# design.net
KiCad netlist of a schematic drawn in Altium Designer
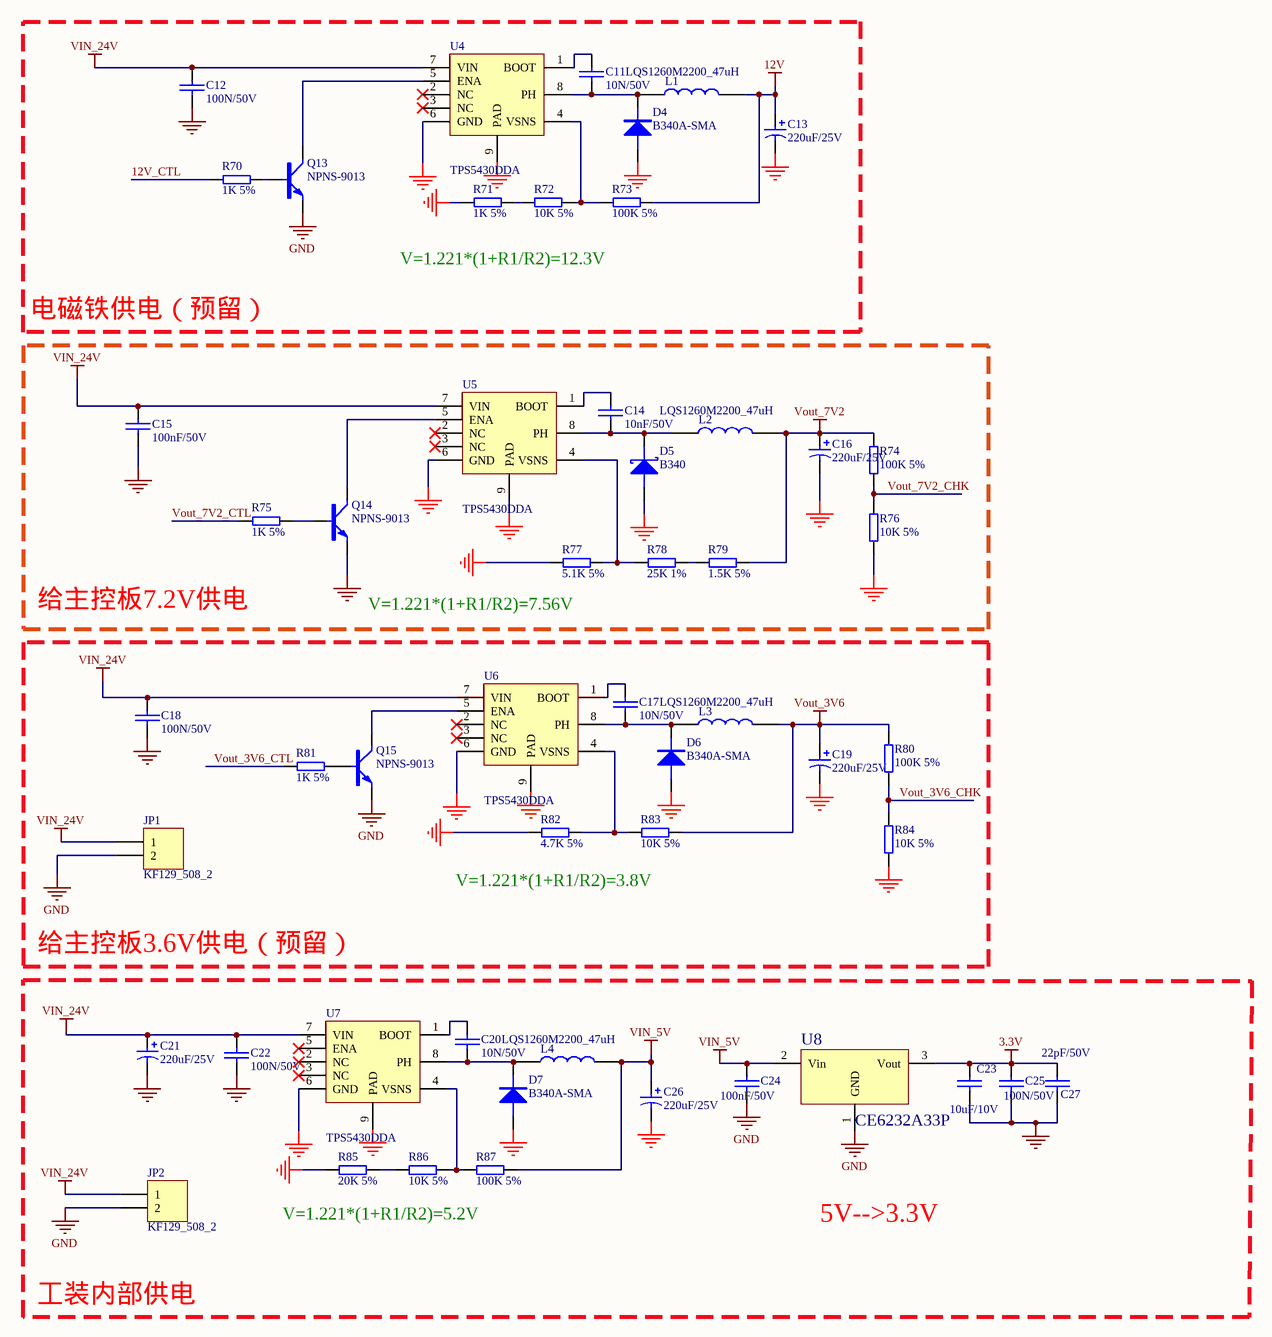
[diagram p0: 电源.SchDoc]

(export (version "E")
  (design (tool "Eeschema 10.0.6"))
  (components
    (comp (ref "C11")
      (value "10N/50V")
      (footprint "CAP0603")
      (description "10N/50V，±10%，0603")
      (fields (field (name "PART NUMBER") "101020103-0007"))
      (libsource (lib "Database_Libs1") (part "CC03K7R9B_10N"))
    )
    (comp (ref "C12")
      (value "100N/50V")
      (footprint "CAP0603")
      (description "100N/50V，±10%，0603")
      (fields (field (name "PART NUMBER") "101020103-0021"))
      (libsource (lib "Database_Libs1") (part "CC03K7R9B_100N"))
    )
    (comp (ref "C13")
      (value "220uF/25V")
      (footprint "220uF 25V")
      (description "220UF,25 V,±20%,8*10mm,立隆电子工业股份有限公司,VEJ221M1ETR-0810")
      (libsource (lib "转接板封装") (part "220uF/25V"))
    )
    (comp (ref "C14")
      (value "10nF/50V")
      (footprint "CAP0603")
      (description "10nF,50 V,±10%,0603,X7R,国巨,CC0603KRX7R9BB103")
      (fields (field (name "PART NUMBER") "101020103-0007"))
      (libsource (lib "Database_Libs2") (part "CC03K7R9_103P"))
    )
    (comp (ref "C15")
      (value "100nF/50V")
      (footprint "CAP0603")
      (description "104pF,50 V,±10%,0603,国巨,CC0603KRX7R9BB104")
      (fields (field (name "PART NUMBER") "101020103-0021"))
      (libsource (lib "Database_Libs2") (part "CC03K7R9_100N"))
    )
    (comp (ref "C16")
      (value "220uF/25V")
      (footprint "220uF 25V")
      (description "220UF,25 V,±20%,8*10mm,立隆电子工业股份有限公司,VEJ221M1ETR-0810")
      (libsource (lib "转接板封装") (part "220uF/25V"))
    )
    (comp (ref "C17")
      (value "10N/50V")
      (footprint "CAP0603")
      (description "10N/50V，±10%，0603")
      (fields (field (name "PART NUMBER") "101020103-0007"))
      (libsource (lib "Database_Libs1") (part "CC03K7R9B_10N"))
    )
    (comp (ref "C18")
      (value "100N/50V")
      (footprint "CAP0603")
      (description "100N/50V，±10%，0603")
      (fields (field (name "PART NUMBER") "101020103-0021"))
      (libsource (lib "Database_Libs1") (part "CC03K7R9B_100N"))
    )
    (comp (ref "C19")
      (value "220uF/25V")
      (footprint "220uF 25V")
      (description "220UF,25 V,±20%,8*10mm,立隆电子工业股份有限公司,VEJ221M1ETR-0810")
      (libsource (lib "转接板封装") (part "220uF/25V"))
    )
    (comp (ref "C20")
      (value "10N/50V")
      (footprint "CAP0603")
      (description "10N/50V，±10%，0603")
      (fields (field (name "PART NUMBER") "101020103-0007"))
      (libsource (lib "Database_Libs1") (part "CC03K7R9B_10N"))
    )
    (comp (ref "C21")
      (value "220uF/25V")
      (footprint "220uF 25V")
      (description "220UF,25 V,±20%,8*10mm,立隆电子工业股份有限公司,VEJ221M1ETR-0810")
      (libsource (lib "转接板封装") (part "220uF/25V"))
    )
    (comp (ref "C22")
      (value "100N/50V")
      (footprint "CAP0603")
      (description "100N/50V，±10%，0603")
      (fields (field (name "PART NUMBER") "101020103-0021"))
      (libsource (lib "Database_Libs1") (part "CC03K7R9B_100N"))
    )
    (comp (ref "C23")
      (value "10uF/10V")
      (footprint "CAP0603")
      (description "106pF,10 V,±10%,0603,村田,GRM188R61A106KE47D")
      (fields (field (name "PART NUMBER") "101020103-0026"))
      (libsource (lib "Database_Libs2") (part "CC03K5R6_10U"))
    )
    (comp (ref "C24")
      (value "100nF/50V")
      (footprint "CAP0603")
      (description "104pF,50 V,±10%,0603,国巨,CC0603KRX7R9BB104")
      (fields (field (name "PART NUMBER") "101020103-0021"))
      (libsource (lib "Database_Libs2") (part "CC03K7R9_100N"))
    )
    (comp (ref "C25")
      (value "100N/50V")
      (footprint "CAP0603")
      (description "100N/50V，±10%，0603")
      (fields (field (name "PART NUMBER") "101020103-0021"))
      (libsource (lib "Database_Libs2") (part "CC03K7R9B_100N"))
    )
    (comp (ref "C26")
      (value "220uF/25V")
      (footprint "220uF 25V")
      (description "220UF,25 V,±20%,8*10mm,立隆电子工业股份有限公司,VEJ221M1ETR-0810")
      (libsource (lib "转接板封装") (part "220uF/25V"))
    )
    (comp (ref "C27")
      (value "22pF/50V")
      (footprint "CAP0603")
      (description "22pF,50 V,±5%,0603,国巨,CC0603JRNPO9BN22")
      (fields (field (name "PART NUMBER") "101020103-0009"))
      (libsource (lib "Database_Libs2") (part "CC03JPO9_22P"))
    )
    (comp (ref "D4")
      (value "B340A-SMA")
      (footprint "DO-214AC")
      (fields (field (name "PART NUMBER") "101040101-0014"))
      (libsource (lib "Database_Libs1") (part "02_B340A-SMA"))
    )
    (comp (ref "D5")
      (value "B340")
      (footprint "DO-214AC")
      (description "B340,SMA,3 A,0.7 V,28 V,DIODES,B340A-13-F")
      (fields (field (name "PART NUMBER") "101040101-0014"))
      (libsource (lib "Database_Libs2") (part "02_B340"))
    )
    (comp (ref "D6")
      (value "B340A-SMA")
      (footprint "DO-214AC")
      (fields (field (name "PART NUMBER") "101040101-0014"))
      (libsource (lib "Database_Libs1") (part "02_B340A-SMA"))
    )
    (comp (ref "D7")
      (value "B340A-SMA")
      (footprint "DO-214AC")
      (fields (field (name "PART NUMBER") "101040101-0014"))
      (libsource (lib "Database_Libs1") (part "02_B340A-SMA"))
    )
    (comp (ref "JP1")
      (value "KF129_508_2")
      (footprint "KF129_508_2")
      (description "KF129-2P,螺丝紧固,2,ABS,松涛")
      (fields (field (name "PART NUMBER") "1010904-0015"))
      (libsource (lib "Database_Libs2") (part "KF129_508_2"))
    )
    (comp (ref "JP2")
      (value "KF129_508_2")
      (footprint "KF129_508_2")
      (description "KF129-2P,螺丝紧固,2,ABS,松涛")
      (fields (field (name "PART NUMBER") "1010904-0015"))
      (libsource (lib "Database_Libs2") (part "KF129_508_2"))
    )
    (comp (ref "L1")
      (value "LQS1260M2200_47uH")
      (footprint "LQS1212")
      (description "47uH/2.2A,±20%，0.072Ω，L1200X1200X600")
      (fields (field (name "PART NUMBER") "1010302-0007"))
      (libsource (lib "Database_Libs1") (part "06_LQS1260M2200_47uH"))
    )
    (comp (ref "L2")
      (value "LQS1260M2200_47uH")
      (footprint "LQS1212")
      (description "47uH/2.2A,±20%，0.072Ω，L1200X1200X600")
      (fields (field (name "PART NUMBER") "1010302-0007"))
      (libsource (lib "Database_Libs1") (part "06_LQS1260M2200_47uH"))
    )
    (comp (ref "L3")
      (value "LQS1260M2200_47uH")
      (footprint "LQS1212")
      (description "47uH/2.2A,±20%，0.072Ω，L1200X1200X600")
      (fields (field (name "PART NUMBER") "1010302-0007"))
      (libsource (lib "Database_Libs1") (part "06_LQS1260M2200_47uH"))
    )
    (comp (ref "L4")
      (value "LQS1260M2200_47uH")
      (footprint "LQS1212")
      (description "47uH/2.2A,±20%，0.072Ω，L1200X1200X600")
      (fields (field (name "PART NUMBER") "1010302-0007"))
      (libsource (lib "Database_Libs1") (part "06_LQS1260M2200_47uH"))
    )
    (comp (ref "Q13")
      (value "NPNS-9013")
      (footprint "SOT-23")
      (description "9013,NPN,SOT-23,长电,S9013")
      (fields (field (name "PART NUMBER") "101040201-0002"))
      (libsource (lib "Database_Libs2") (part "03_NPNS-9013"))
    )
    (comp (ref "Q14")
      (value "NPNS-9013")
      (footprint "SOT-23")
      (description "9013,NPN,SOT-23,长电,S9013")
      (fields (field (name "PART NUMBER") "101040201-0002"))
      (libsource (lib "Database_Libs2") (part "03_NPNS-9013"))
    )
    (comp (ref "Q15")
      (value "NPNS-9013")
      (footprint "SOT-23")
      (description "9013,NPN,SOT-23,长电,S9013")
      (fields (field (name "PART NUMBER") "101040201-0002"))
      (libsource (lib "Database_Libs2") (part "03_NPNS-9013"))
    )
    (comp (ref "R70")
      (value "1K 5%")
      (footprint "RES0603")
      (description "1K,±5%,1/10W,0603,国巨,RC0603JR-071KL")
      (fields (field (name "PART NUMBER") "101010103-0008"))
      (libsource (lib "Database_Libs2") (part "RC03J_1K"))
    )
    (comp (ref "R71")
      (value "1K 5%")
      (footprint "RES0603")
      (description "1K,±5%,1/10W,0603,国巨,RC0603JR-071KL")
      (fields (field (name "PART NUMBER") "101010103-0008"))
      (libsource (lib "Database_Libs2") (part "RC03J_1K"))
    )
    (comp (ref "R72")
      (value "10K 5%")
      (footprint "RES0603")
      (description "国巨,±5%,0603,,155 ℃,-55 ℃,RC0603JR-0710KL,无铅,200 ppm/℃,1/10W,,10K")
      (fields (field (name "PART NUMBER") "101010103-0003"))
      (libsource (lib "Database_Libs2") (part "RC03J_10K"))
    )
    (comp (ref "R73")
      (value "100K 5%")
      (footprint "RES0603")
      (description "国巨,±5%,0603,,155 ℃,-55 ℃,RC0603JR-07100KL,无铅,100 ppm/℃,1/10W,,100K")
      (fields (field (name "PART NUMBER") "101010103-0005"))
      (libsource (lib "Database_Libs2") (part "RC03J_100K"))
    )
    (comp (ref "R74")
      (value "100K 5%")
      (footprint "RES0603")
      (description "国巨,±5%,0603,,155 ℃,-55 ℃,RC0603JR-07100KL,无铅,100 ppm/℃,1/10W,,100K")
      (fields (field (name "PART NUMBER") "101010103-0005"))
      (libsource (lib "Database_Libs2") (part "RC03J_100K"))
    )
    (comp (ref "R75")
      (value "1K 5%")
      (footprint "RES0603")
      (description "1K,±5%,1/10W,0603,国巨,RC0603JR-071KL")
      (fields (field (name "PART NUMBER") "101010103-0008"))
      (libsource (lib "Database_Libs2") (part "RC03J_1K"))
    )
    (comp (ref "R76")
      (value "10K 5%")
      (footprint "RES0603")
      (description "国巨,±5%,0603,,155 ℃,-55 ℃,RC0603JR-0710KL,无铅,200 ppm/℃,1/10W,,10K")
      (fields (field (name "PART NUMBER") "101010103-0003"))
      (libsource (lib "Database_Libs2") (part "RC03J_10K"))
    )
    (comp (ref "R77")
      (value "5.1K 5%")
      (footprint "RES0603")
      (description "国巨,±5%,0603,,155 ℃,55 ℃,RC0603JR-075.1KL,无铅,200 ppm/℃,1/10W,,5.1k")
      (fields (field (name "PART NUMBER") "101010103-0015"))
      (libsource (lib "Database_Libs2") (part "RC03J_5.1K"))
    )
    (comp (ref "R78")
      (value "25K 1%")
      (footprint "RES0603")
      (description "25K±1%,1/10W,0603")
      (fields (field (name "PART NUMBER") "101010103-0056"))
      (libsource (lib "转接板封装") (part "RC03J_25K"))
    )
    (comp (ref "R79")
      (value "1.5K 5%")
      (footprint "RES0603")
      (description "1.5K,±5%,1/10W,0603,国巨,RC0603JR-071K5L")
      (fields (field (name "PART NUMBER") "101010103-0013"))
      (libsource (lib "转接板封装") (part "RC03J_1.5K"))
    )
    (comp (ref "R80")
      (value "100K 5%")
      (footprint "RES0603")
      (description "100K±5%,1/10W,0603")
      (fields (field (name "PART NUMBER") "101010103-0005"))
      (libsource (lib "Database_Libs1") (part "RC03JF_100K"))
    )
    (comp (ref "R81")
      (value "1K 5%")
      (footprint "RES0603")
      (description "1K,±5%,1/10W,0603,国巨,RC0603JR-071KL")
      (fields (field (name "PART NUMBER") "101010103-0008"))
      (libsource (lib "Database_Libs2") (part "RC03J_1K"))
    )
    (comp (ref "R82")
      (value "4.7K 5%")
      (footprint "RES0603")
      (description "4.7K±5%,1/10W,0603")
      (fields (field (name "PART NUMBER") "101010103-0042"))
      (libsource (lib "Database_Libs2") (part "RC03J_4.7K"))
    )
    (comp (ref "R83")
      (value "10K 5%")
      (footprint "RES0603")
      (description "国巨,±5%,0603,,155 ℃,-55 ℃,RC0603JR-0710KL,无铅,200 ppm/℃,1/10W,,10K")
      (fields (field (name "PART NUMBER") "101010103-0003"))
      (libsource (lib "Database_Libs2") (part "RC03J_10K"))
    )
    (comp (ref "R84")
      (value "10K 5%")
      (footprint "RES0603")
      (description "国巨,±5%,0603,,155 ℃,-55 ℃,RC0603JR-0710KL,无铅,200 ppm/℃,1/10W,,10K")
      (fields (field (name "PART NUMBER") "101010103-0003"))
      (libsource (lib "Database_Libs2") (part "RC03J_10K"))
    )
    (comp (ref "R85")
      (value "20K 5%")
      (footprint "RES0603")
      (description "国巨,±5%,0603,,155 ℃,-55 ℃,RC0603JR-0720KL,无铅,200 ppm/℃,1/10W,,20K")
      (fields (field (name "PART NUMBER") "101010103-0004"))
      (libsource (lib "Database_Libs2") (part "RC03J_20K"))
    )
    (comp (ref "R86")
      (value "10K 5%")
      (footprint "RES0603")
      (description "国巨,±5%,0603,,155 ℃,-55 ℃,RC0603JR-0710KL,无铅,200 ppm/℃,1/10W,,10K")
      (fields (field (name "PART NUMBER") "101010103-0003"))
      (libsource (lib "Database_Libs2") (part "RC03J_10K"))
    )
    (comp (ref "R87")
      (value "100K 5%")
      (footprint "RES0603")
      (description "100K±5%,1/10W,0603")
      (fields (field (name "PART NUMBER") "101010103-0005"))
      (libsource (lib "Database_Libs1") (part "RC03JF_100K"))
    )
    (comp (ref "U4")
      (value "TPS5430DDA")
      (footprint "SOP-8-P")
      (description "TPS5430DDA,SOP8,TI,TPS5430DDA")
      (fields (field (name "PART NUMBER") "101050101-0053"))
      (libsource (lib "Database_Libs2") (part "02_TPS5430DDA"))
    )
    (comp (ref "U5")
      (value "TPS5430DDA")
      (footprint "SOP-8-P")
      (description "TPS5430DDA,SOP8,TI,TPS5430DDA")
      (fields (field (name "PART NUMBER") "101050101-0053"))
      (libsource (lib "Database_Libs2") (part "02_TPS5430DDA"))
    )
    (comp (ref "U6")
      (value "TPS5430DDA")
      (footprint "SOP-8-P")
      (description "TPS5430DDA,SOP8,TI,TPS5430DDA")
      (fields (field (name "PART NUMBER") "101050101-0053"))
      (libsource (lib "Database_Libs2") (part "02_TPS5430DDA"))
    )
    (comp (ref "U7")
      (value "TPS5430DDA")
      (footprint "SOP-8-P")
      (description "TPS5430DDA,SOP8,TI,TPS5430DDA")
      (fields (field (name "PART NUMBER") "101050101-0053"))
      (libsource (lib "Database_Libs2") (part "02_TPS5430DDA"))
    )
    (comp (ref "U8")
      (value "CE6232A33P")
      (footprint "SOT-89")
      (description "CE6232-3.3,CE6232-3.3,SOT89-3,8V,1.8V,0.11V,3.3V,300mA,0.8uA,南京芯力微电子有限公司")
      (fields (field (name "PART NUMBER") "1010503-0029"))
      (libsource (lib "Database_Libs2") (part "02_CE6232A33P"))
    )
  )
  (nets
    (net (code "1") (name "/12V_CTL") (class "Default")
      (node (ref "R70") (pin "1") (pinfunction "1_1") (pintype "passive"))
    )
    (net (code "2") (name "/Vout_3V6_CHK") (class "Default")
      (node (ref "R80") (pin "1") (pinfunction "1_1") (pintype "passive"))
      (node (ref "R84") (pin "2") (pinfunction "2_2") (pintype "passive"))
    )
    (net (code "3") (name "/Vout_3V6_CTL") (class "Default")
      (node (ref "R81") (pin "1") (pinfunction "1_1") (pintype "passive"))
    )
    (net (code "4") (name "/Vout_7V2_CHK") (class "Default")
      (node (ref "R74") (pin "1") (pinfunction "1_1") (pintype "passive"))
      (node (ref "R76") (pin "2") (pinfunction "2_2") (pintype "passive"))
    )
    (net (code "5") (name "/Vout_7V2_CTL") (class "Default")
      (node (ref "R75") (pin "1") (pinfunction "1_1") (pintype "passive"))
    )
    (net (code "6") (name "3.3V") (class "Default")
      (node (ref "C23") (pin "1") (pinfunction "1_1") (pintype "passive"))
      (node (ref "C25") (pin "1") (pinfunction "1_1") (pintype "passive"))
      (node (ref "C27") (pin "1") (pinfunction "1_1") (pintype "passive"))
      (node (ref "U8") (pin "3") (pinfunction "Vout_3") (pintype "passive"))
    )
    (net (code "7") (name "12V") (class "Default")
      (node (ref "C13") (pin "1") (pinfunction "1_1") (pintype "passive"))
      (node (ref "L1") (pin "2") (pinfunction "2_2") (pintype "passive"))
      (node (ref "R73") (pin "2") (pinfunction "2_2") (pintype "passive"))
    )
    (net (code "8") (name "GND") (class "Default")
      (node (ref "C12") (pin "2") (pinfunction "2_2") (pintype "passive"))
      (node (ref "C13") (pin "2") (pinfunction "2_2") (pintype "passive"))
      (node (ref "C15") (pin "2") (pinfunction "2_2") (pintype "passive"))
      (node (ref "C16") (pin "2") (pinfunction "2_2") (pintype "passive"))
      (node (ref "C18") (pin "2") (pinfunction "2_2") (pintype "passive"))
      (node (ref "C19") (pin "2") (pinfunction "2_2") (pintype "passive"))
      (node (ref "C21") (pin "2") (pinfunction "2_2") (pintype "passive"))
      (node (ref "C22") (pin "2") (pinfunction "2_2") (pintype "passive"))
      (node (ref "C23") (pin "2") (pinfunction "2_2") (pintype "passive"))
      (node (ref "C24") (pin "2") (pinfunction "2_2") (pintype "passive"))
      (node (ref "C25") (pin "2") (pinfunction "2_2") (pintype "passive"))
      (node (ref "C26") (pin "2") (pinfunction "2_2") (pintype "passive"))
      (node (ref "C27") (pin "2") (pinfunction "2_2") (pintype "passive"))
      (node (ref "D4") (pin "1") (pinfunction "1_1") (pintype "passive"))
      (node (ref "D5") (pin "1") (pinfunction "1_1") (pintype "passive"))
      (node (ref "D6") (pin "1") (pinfunction "1_1") (pintype "passive"))
      (node (ref "D7") (pin "1") (pinfunction "1_1") (pintype "passive"))
      (node (ref "JP1") (pin "2") (pinfunction "2_2") (pintype "passive"))
      (node (ref "JP2") (pin "2") (pinfunction "2_2") (pintype "passive"))
      (node (ref "Q13") (pin "2") (pinfunction "E_2") (pintype "passive"))
      (node (ref "Q14") (pin "2") (pinfunction "E_2") (pintype "passive"))
      (node (ref "Q15") (pin "2") (pinfunction "E_2") (pintype "passive"))
      (node (ref "R71") (pin "1") (pinfunction "1_1") (pintype "passive"))
      (node (ref "R76") (pin "1") (pinfunction "1_1") (pintype "passive"))
      (node (ref "R77") (pin "1") (pinfunction "1_1") (pintype "passive"))
      (node (ref "R82") (pin "1") (pinfunction "1_1") (pintype "passive"))
      (node (ref "R84") (pin "1") (pinfunction "1_1") (pintype "passive"))
      (node (ref "R85") (pin "1") (pinfunction "1_1") (pintype "passive"))
      (node (ref "U4") (pin "6") (pinfunction "GND_6") (pintype "passive"))
      (node (ref "U4") (pin "9") (pinfunction "PAD_9") (pintype "passive"))
      (node (ref "U5") (pin "6") (pinfunction "GND_6") (pintype "passive"))
      (node (ref "U5") (pin "9") (pinfunction "PAD_9") (pintype "passive"))
      (node (ref "U6") (pin "6") (pinfunction "GND_6") (pintype "passive"))
      (node (ref "U6") (pin "9") (pinfunction "PAD_9") (pintype "passive"))
      (node (ref "U7") (pin "6") (pinfunction "GND_6") (pintype "passive"))
      (node (ref "U7") (pin "9") (pinfunction "PAD_9") (pintype "passive"))
      (node (ref "U8") (pin "1") (pinfunction "GND_1") (pintype "passive"))
    )
    (net (code "9") (name "Net-(Q13-B)") (class "Default")
      (node (ref "Q13") (pin "1") (pinfunction "B_1") (pintype "passive"))
      (node (ref "R70") (pin "2") (pinfunction "2_2") (pintype "passive"))
    )
    (net (code "10") (name "Net-(Q13-C)") (class "Default")
      (node (ref "Q13") (pin "3") (pinfunction "C_3") (pintype "passive"))
      (node (ref "U4") (pin "5") (pinfunction "ENA_5") (pintype "passive"))
    )
    (net (code "11") (name "Net-(Q14-B)") (class "Default")
      (node (ref "Q14") (pin "1") (pinfunction "B_1") (pintype "passive"))
      (node (ref "R75") (pin "2") (pinfunction "2_2") (pintype "passive"))
    )
    (net (code "12") (name "Net-(Q14-C)") (class "Default")
      (node (ref "Q14") (pin "3") (pinfunction "C_3") (pintype "passive"))
      (node (ref "U5") (pin "5") (pinfunction "ENA_5") (pintype "passive"))
    )
    (net (code "13") (name "Net-(Q15-B)") (class "Default")
      (node (ref "Q15") (pin "1") (pinfunction "B_1") (pintype "passive"))
      (node (ref "R81") (pin "2") (pinfunction "2_2") (pintype "passive"))
    )
    (net (code "14") (name "Net-(Q15-C)") (class "Default")
      (node (ref "Q15") (pin "3") (pinfunction "C_3") (pintype "passive"))
      (node (ref "U6") (pin "5") (pinfunction "ENA_5") (pintype "passive"))
    )
    (net (code "15") (name "Net-(R71-Pad2)") (class "Default")
      (node (ref "R71") (pin "2") (pinfunction "2_2") (pintype "passive"))
      (node (ref "R72") (pin "1") (pinfunction "1_1") (pintype "passive"))
    )
    (net (code "16") (name "Net-(R78-Pad2)") (class "Default")
      (node (ref "R78") (pin "2") (pinfunction "2_2") (pintype "passive"))
      (node (ref "R79") (pin "1") (pinfunction "1_1") (pintype "passive"))
    )
    (net (code "17") (name "Net-(R85-Pad2)") (class "Default")
      (node (ref "R85") (pin "2") (pinfunction "2_2") (pintype "passive"))
      (node (ref "R86") (pin "1") (pinfunction "1_1") (pintype "passive"))
    )
    (net (code "18") (name "Net-(U4-BOOT)") (class "Default")
      (node (ref "C11") (pin "2") (pinfunction "2_2") (pintype "passive"))
      (node (ref "U4") (pin "1") (pinfunction "BOOT_1") (pintype "passive"))
    )
    (net (code "19") (name "Net-(U4-PH)") (class "Default")
      (node (ref "C11") (pin "1") (pinfunction "1_1") (pintype "passive"))
      (node (ref "D4") (pin "2") (pinfunction "2_2") (pintype "passive"))
      (node (ref "L1") (pin "1") (pinfunction "1_1") (pintype "passive"))
      (node (ref "U4") (pin "8") (pinfunction "PH_8") (pintype "passive"))
    )
    (net (code "20") (name "Net-(U4-VSNS)") (class "Default")
      (node (ref "R72") (pin "2") (pinfunction "2_2") (pintype "passive"))
      (node (ref "R73") (pin "1") (pinfunction "1_1") (pintype "passive"))
      (node (ref "U4") (pin "4") (pinfunction "VSNS_4") (pintype "passive"))
    )
    (net (code "21") (name "Net-(U5-BOOT)") (class "Default")
      (node (ref "C14") (pin "2") (pinfunction "2_2") (pintype "passive"))
      (node (ref "U5") (pin "1") (pinfunction "BOOT_1") (pintype "passive"))
    )
    (net (code "22") (name "Net-(U5-PH)") (class "Default")
      (node (ref "C14") (pin "1") (pinfunction "1_1") (pintype "passive"))
      (node (ref "D5") (pin "2") (pinfunction "2_2") (pintype "passive"))
      (node (ref "L2") (pin "1") (pinfunction "1_1") (pintype "passive"))
      (node (ref "U5") (pin "8") (pinfunction "PH_8") (pintype "passive"))
    )
    (net (code "23") (name "Net-(U5-VSNS)") (class "Default")
      (node (ref "R77") (pin "2") (pinfunction "2_2") (pintype "passive"))
      (node (ref "R78") (pin "1") (pinfunction "1_1") (pintype "passive"))
      (node (ref "U5") (pin "4") (pinfunction "VSNS_4") (pintype "passive"))
    )
    (net (code "24") (name "Net-(U6-BOOT)") (class "Default")
      (node (ref "C17") (pin "2") (pinfunction "2_2") (pintype "passive"))
      (node (ref "U6") (pin "1") (pinfunction "BOOT_1") (pintype "passive"))
    )
    (net (code "25") (name "Net-(U6-PH)") (class "Default")
      (node (ref "C17") (pin "1") (pinfunction "1_1") (pintype "passive"))
      (node (ref "D6") (pin "2") (pinfunction "2_2") (pintype "passive"))
      (node (ref "L3") (pin "1") (pinfunction "1_1") (pintype "passive"))
      (node (ref "U6") (pin "8") (pinfunction "PH_8") (pintype "passive"))
    )
    (net (code "26") (name "Net-(U6-VSNS)") (class "Default")
      (node (ref "R82") (pin "2") (pinfunction "2_2") (pintype "passive"))
      (node (ref "R83") (pin "1") (pinfunction "1_1") (pintype "passive"))
      (node (ref "U6") (pin "4") (pinfunction "VSNS_4") (pintype "passive"))
    )
    (net (code "27") (name "Net-(U7-BOOT)") (class "Default")
      (node (ref "C20") (pin "2") (pinfunction "2_2") (pintype "passive"))
      (node (ref "U7") (pin "1") (pinfunction "BOOT_1") (pintype "passive"))
    )
    (net (code "28") (name "Net-(U7-PH)") (class "Default")
      (node (ref "C20") (pin "1") (pinfunction "1_1") (pintype "passive"))
      (node (ref "D7") (pin "2") (pinfunction "2_2") (pintype "passive"))
      (node (ref "L4") (pin "1") (pinfunction "1_1") (pintype "passive"))
      (node (ref "U7") (pin "8") (pinfunction "PH_8") (pintype "passive"))
    )
    (net (code "29") (name "Net-(U7-VSNS)") (class "Default")
      (node (ref "R86") (pin "2") (pinfunction "2_2") (pintype "passive"))
      (node (ref "R87") (pin "2") (pinfunction "2_2") (pintype "passive"))
      (node (ref "U7") (pin "4") (pinfunction "VSNS_4") (pintype "passive"))
    )
    (net (code "30") (name "VIN_5V") (class "Default")
      (node (ref "C24") (pin "1") (pinfunction "1_1") (pintype "passive"))
      (node (ref "C26") (pin "1") (pinfunction "1_1") (pintype "passive"))
      (node (ref "L4") (pin "2") (pinfunction "2_2") (pintype "passive"))
      (node (ref "R87") (pin "1") (pinfunction "1_1") (pintype "passive"))
      (node (ref "U8") (pin "2") (pinfunction "Vin_2") (pintype "passive"))
    )
    (net (code "31") (name "VIN_24V") (class "Default")
      (node (ref "C12") (pin "1") (pinfunction "1_1") (pintype "passive"))
      (node (ref "C15") (pin "1") (pinfunction "1_1") (pintype "passive"))
      (node (ref "C18") (pin "1") (pinfunction "1_1") (pintype "passive"))
      (node (ref "C21") (pin "1") (pinfunction "1_1") (pintype "passive"))
      (node (ref "C22") (pin "1") (pinfunction "1_1") (pintype "passive"))
      (node (ref "JP1") (pin "1") (pinfunction "1_1") (pintype "passive"))
      (node (ref "JP2") (pin "1") (pinfunction "1_1") (pintype "passive"))
      (node (ref "U4") (pin "7") (pinfunction "VIN_7") (pintype "passive"))
      (node (ref "U5") (pin "7") (pinfunction "VIN_7") (pintype "passive"))
      (node (ref "U6") (pin "7") (pinfunction "VIN_7") (pintype "passive"))
      (node (ref "U7") (pin "7") (pinfunction "VIN_7") (pintype "passive"))
    )
    (net (code "32") (name "Vout_3V6") (class "Default")
      (node (ref "C19") (pin "1") (pinfunction "1_1") (pintype "passive"))
      (node (ref "L3") (pin "2") (pinfunction "2_2") (pintype "passive"))
      (node (ref "R80") (pin "2") (pinfunction "2_2") (pintype "passive"))
      (node (ref "R83") (pin "2") (pinfunction "2_2") (pintype "passive"))
    )
    (net (code "33") (name "Vout_7V2") (class "Default")
      (node (ref "C16") (pin "1") (pinfunction "1_1") (pintype "passive"))
      (node (ref "L2") (pin "2") (pinfunction "2_2") (pintype "passive"))
      (node (ref "R74") (pin "2") (pinfunction "2_2") (pintype "passive"))
      (node (ref "R79") (pin "2") (pinfunction "2_2") (pintype "passive"))
    )
    (net (code "34") (name "unconnected-(U4-NC-Pad2)") (class "Default")
      (node (ref "U4") (pin "2") (pinfunction "NC_2") (pintype "passive+no_connect"))
    )
    (net (code "35") (name "unconnected-(U4-NC-Pad3)") (class "Default")
      (node (ref "U4") (pin "3") (pinfunction "NC_3") (pintype "passive+no_connect"))
    )
    (net (code "36") (name "unconnected-(U5-NC-Pad2)") (class "Default")
      (node (ref "U5") (pin "2") (pinfunction "NC_2") (pintype "passive+no_connect"))
    )
    (net (code "37") (name "unconnected-(U5-NC-Pad3)") (class "Default")
      (node (ref "U5") (pin "3") (pinfunction "NC_3") (pintype "passive+no_connect"))
    )
    (net (code "38") (name "unconnected-(U6-NC-Pad2)") (class "Default")
      (node (ref "U6") (pin "2") (pinfunction "NC_2") (pintype "passive+no_connect"))
    )
    (net (code "39") (name "unconnected-(U6-NC-Pad3)") (class "Default")
      (node (ref "U6") (pin "3") (pinfunction "NC_3") (pintype "passive+no_connect"))
    )
    (net (code "40") (name "unconnected-(U7-ENA-Pad5)") (class "Default")
      (node (ref "U7") (pin "5") (pinfunction "ENA_5") (pintype "passive+no_connect"))
    )
    (net (code "41") (name "unconnected-(U7-NC-Pad2)") (class "Default")
      (node (ref "U7") (pin "2") (pinfunction "NC_2") (pintype "passive+no_connect"))
    )
    (net (code "42") (name "unconnected-(U7-NC-Pad3)") (class "Default")
      (node (ref "U7") (pin "3") (pinfunction "NC_3") (pintype "passive+no_connect"))
    )
  )
)
